# Arduino1.net
KiCad netlist of a schematic drawn in EAGLE
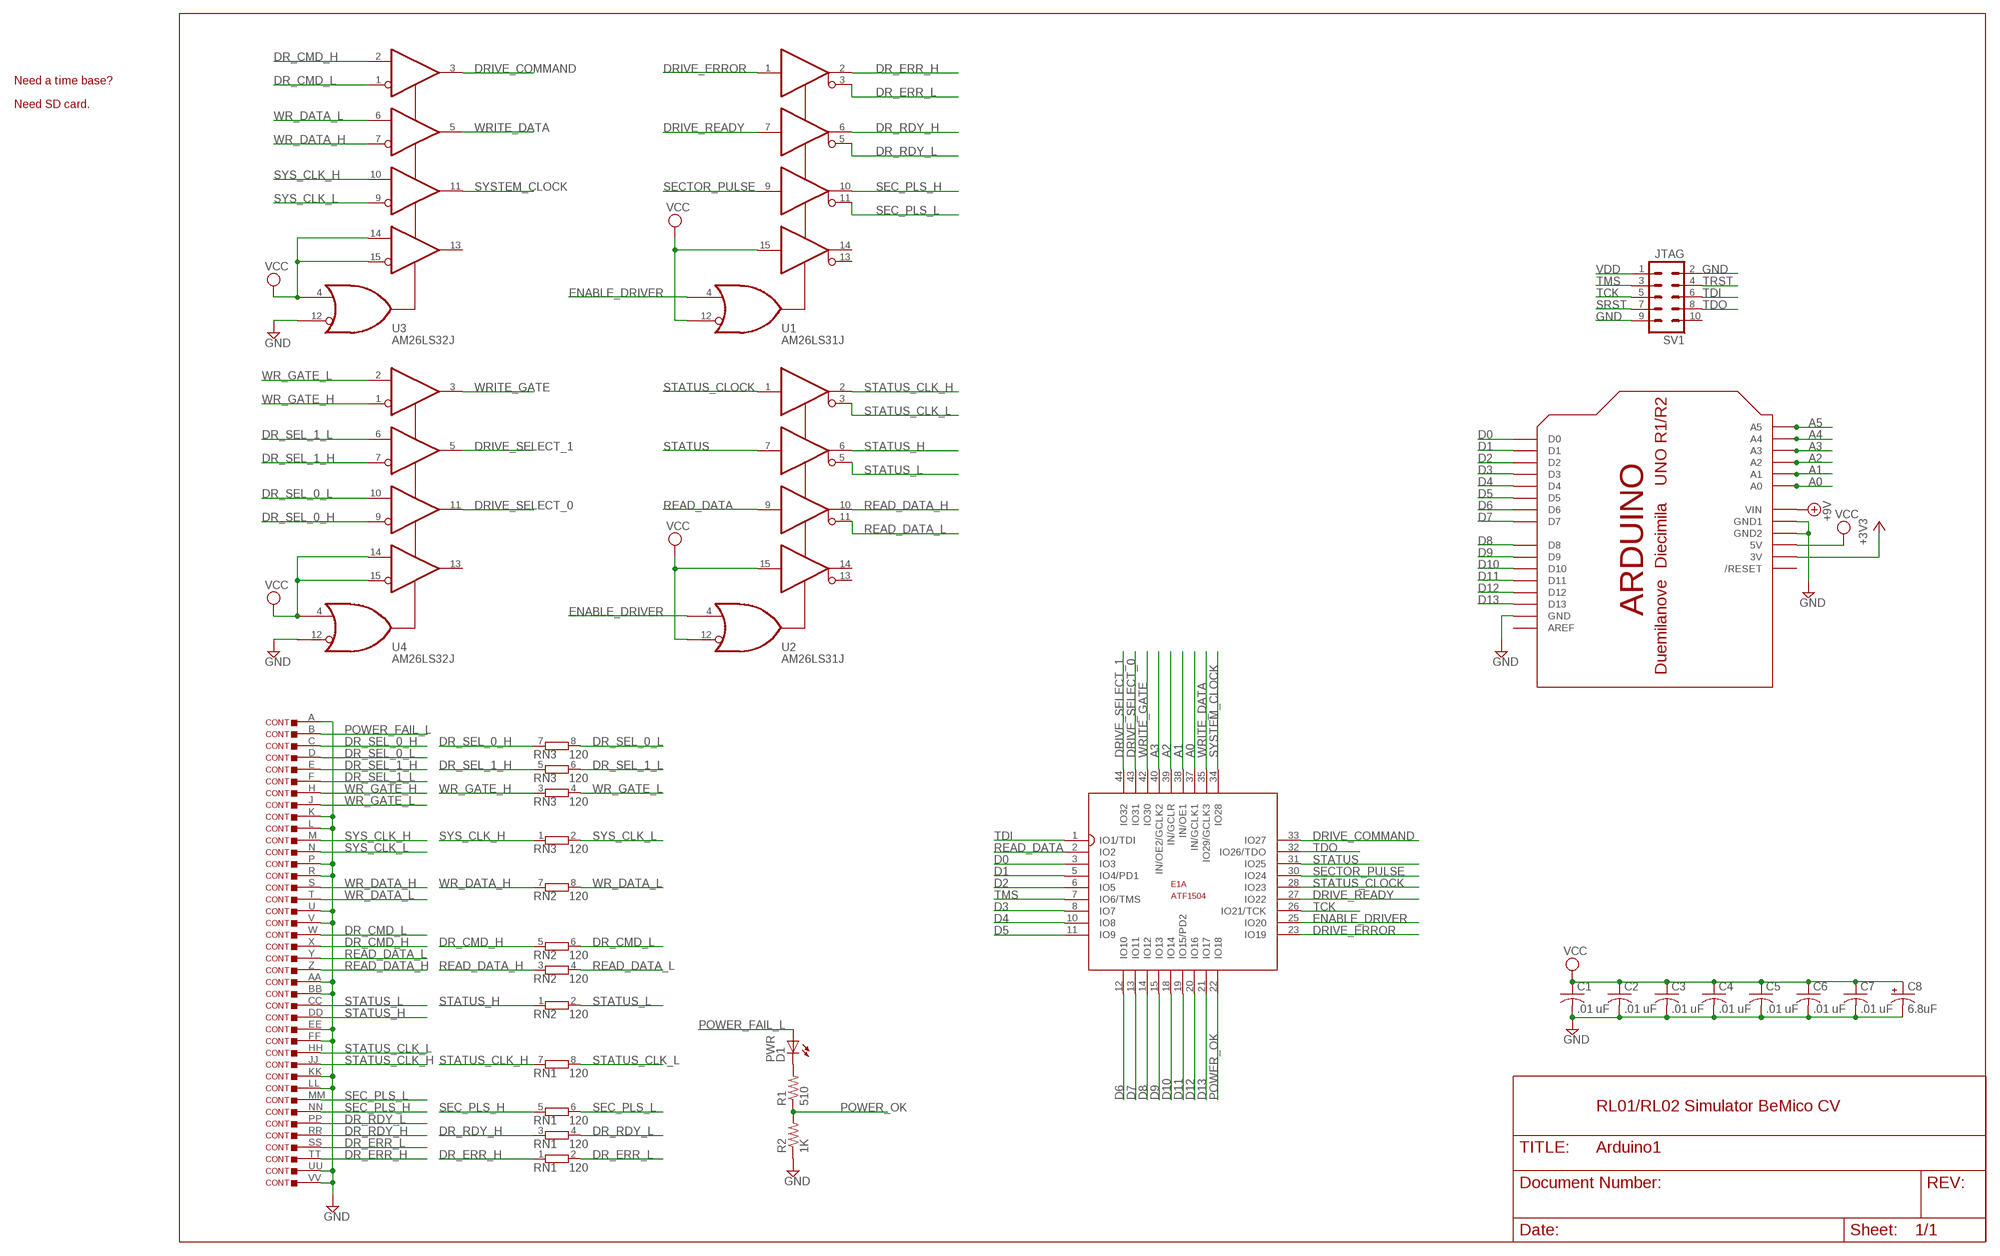
[diagram p0: schematic, sheet 1]

(export (version "E")
  (design (tool "Eeschema 10.0.6"))
  (components
    (comp (ref "C1")
      (value ".01 uF")
      (footprint "eagle-import:C050-025X075")
      (libsource (lib "eagle-import") (part "C-US050-025X075"))
    )
    (comp (ref "C2")
      (value ".01 uF")
      (footprint "eagle-import:C050-025X075")
      (libsource (lib "eagle-import") (part "C-US050-025X075"))
    )
    (comp (ref "C3")
      (value ".01 uF")
      (footprint "eagle-import:C050-025X075")
      (libsource (lib "eagle-import") (part "C-US050-025X075"))
    )
    (comp (ref "C4")
      (value ".01 uF")
      (footprint "eagle-import:C050-025X075")
      (libsource (lib "eagle-import") (part "C-US050-025X075"))
    )
    (comp (ref "C5")
      (value ".01 uF")
      (footprint "eagle-import:C050-025X075")
      (libsource (lib "eagle-import") (part "C-US050-025X075"))
    )
    (comp (ref "C6")
      (value ".01 uF")
      (footprint "eagle-import:C050-025X075")
      (libsource (lib "eagle-import") (part "C-US050-025X075"))
    )
    (comp (ref "C7")
      (value ".01 uF")
      (footprint "eagle-import:C050-025X075")
      (libsource (lib "eagle-import") (part "C-US050-025X075"))
    )
    (comp (ref "C8")
      (value "6.8uF")
      (footprint "eagle-import:E5-5")
      (libsource (lib "eagle-import") (part "CPOL-USE5-5"))
    )
    (comp (ref "CONT")
      (value "DEC40PINSV")
      (footprint "eagle-import:DEC40PINV")
      (libsource (lib "eagle-import") (part "DEC40PINSV"))
    )
    (comp (ref "D1")
      (value "PWR")
      (footprint "eagle-import:LED5MM")
      (libsource (lib "eagle-import") (part "LED5MM"))
    )
    (comp (ref "E1")
      (value "ATF1504")
      (footprint "eagle-import:TQFP44")
      (libsource (lib "eagle-import") (part "ATF150X44TQFP"))
    )
    (comp (ref "R1")
      (value "510")
      (footprint "eagle-import:0207_10")
      (libsource (lib "eagle-import") (part "R-US_0207/10"))
    )
    (comp (ref "R2")
      (value "1K")
      (footprint "eagle-import:0207_10")
      (libsource (lib "eagle-import") (part "R-US_0207/10"))
    )
    (comp (ref "RN1")
      (value "120")
      (footprint "eagle-import:SIL8")
      (libsource (lib "eagle-import") (part "E4RP"))
    )
    (comp (ref "RN2")
      (value "120")
      (footprint "eagle-import:SIL8")
      (libsource (lib "eagle-import") (part "E4RP"))
    )
    (comp (ref "RN3")
      (value "120")
      (footprint "eagle-import:SIL8")
      (libsource (lib "eagle-import") (part "E4RP"))
    )
    (comp (ref "SV1")
      (value "JTAG")
      (footprint "eagle-import:ML10")
      (libsource (lib "eagle-import") (part "ML10"))
    )
    (comp (ref "U$3")
      (value "ARDUINOUNO")
      (footprint "eagle-import:ARDUINO")
      (libsource (lib "eagle-import") (part "ARDUINOUNO"))
    )
    (comp (ref "U1")
      (value "AM26LS31J")
      (footprint "eagle-import:SO16")
      (libsource (lib "eagle-import") (part "AM26LS31J"))
    )
    (comp (ref "U2")
      (value "AM26LS31J")
      (footprint "eagle-import:SO16")
      (libsource (lib "eagle-import") (part "AM26LS31J"))
    )
    (comp (ref "U3")
      (value "AM26LS32J")
      (footprint "eagle-import:SO16")
      (libsource (lib "eagle-import") (part "AM26LS32J"))
    )
    (comp (ref "U4")
      (value "AM26LS32J")
      (footprint "eagle-import:SO16")
      (libsource (lib "eagle-import") (part "AM26LS32J"))
    )
  )
  (nets
    (net (code "1") (name "+3V3") (class "Default")
      (node (ref "U$3") (pin "3V") (pinfunction "3V_3V") (pintype "power_in"))
    )
    (net (code "2") (name "+9V") (class "Default")
      (node (ref "U$3") (pin "VIN") (pinfunction "VIN_VIN") (pintype "power_in"))
    )
    (net (code "3") (name "/A0") (class "Default")
      (node (ref "E1") (pin "37") (pinfunction "IN/GCLK1_37") (pintype "input"))
      (node (ref "U$3") (pin "A0") (pinfunction "A0_A0") (pintype "bidirectional"))
    )
    (net (code "4") (name "/A1") (class "Default")
      (node (ref "E1") (pin "38") (pinfunction "IN/OE1_38") (pintype "input"))
      (node (ref "U$3") (pin "A1") (pinfunction "A1_A1") (pintype "bidirectional"))
    )
    (net (code "5") (name "/A2") (class "Default")
      (node (ref "E1") (pin "39") (pinfunction "IN/GCLR_39") (pintype "input"))
      (node (ref "U$3") (pin "A2") (pinfunction "A2_A2") (pintype "bidirectional"))
    )
    (net (code "6") (name "/A3") (class "Default")
      (node (ref "E1") (pin "40") (pinfunction "IN/OE2/GCLK2_40") (pintype "input"))
      (node (ref "U$3") (pin "A3") (pinfunction "A3_A3") (pintype "bidirectional"))
    )
    (net (code "7") (name "/A4") (class "Default")
      (node (ref "U$3") (pin "A4") (pinfunction "A4_A4") (pintype "bidirectional"))
    )
    (net (code "8") (name "/A5") (class "Default")
      (node (ref "U$3") (pin "A5") (pinfunction "A5_A5") (pintype "bidirectional"))
    )
    (net (code "9") (name "/D0") (class "Default")
      (node (ref "E1") (pin "3") (pinfunction "IO3_3") (pintype "bidirectional"))
      (node (ref "U$3") (pin "D0") (pinfunction "D0_D0") (pintype "bidirectional"))
    )
    (net (code "10") (name "/D1") (class "Default")
      (node (ref "E1") (pin "5") (pinfunction "IO4/PD1_5") (pintype "bidirectional"))
      (node (ref "U$3") (pin "D1") (pinfunction "D1_D1") (pintype "bidirectional"))
    )
    (net (code "11") (name "/D2") (class "Default")
      (node (ref "E1") (pin "6") (pinfunction "IO5_6") (pintype "bidirectional"))
      (node (ref "U$3") (pin "D2") (pinfunction "D2_D2") (pintype "bidirectional"))
    )
    (net (code "12") (name "/D3") (class "Default")
      (node (ref "E1") (pin "8") (pinfunction "IO7_8") (pintype "bidirectional"))
      (node (ref "U$3") (pin "D3") (pinfunction "D3_D3") (pintype "bidirectional"))
    )
    (net (code "13") (name "/D4") (class "Default")
      (node (ref "E1") (pin "10") (pinfunction "IO8_10") (pintype "bidirectional"))
      (node (ref "U$3") (pin "D4") (pinfunction "D4_D4") (pintype "bidirectional"))
    )
    (net (code "14") (name "/D5") (class "Default")
      (node (ref "E1") (pin "11") (pinfunction "IO9_11") (pintype "bidirectional"))
      (node (ref "U$3") (pin "D5") (pinfunction "D5_D5") (pintype "bidirectional"))
    )
    (net (code "15") (name "/D6") (class "Default")
      (node (ref "E1") (pin "12") (pinfunction "IO10_12") (pintype "bidirectional"))
      (node (ref "U$3") (pin "D6") (pinfunction "D6_D6") (pintype "bidirectional"))
    )
    (net (code "16") (name "/D7") (class "Default")
      (node (ref "E1") (pin "13") (pinfunction "IO11_13") (pintype "bidirectional"))
      (node (ref "U$3") (pin "D7") (pinfunction "D7_D7") (pintype "bidirectional"))
    )
    (net (code "17") (name "/D8") (class "Default")
      (node (ref "E1") (pin "14") (pinfunction "IO12_14") (pintype "bidirectional"))
      (node (ref "U$3") (pin "D8") (pinfunction "D8_D8") (pintype "bidirectional"))
    )
    (net (code "18") (name "/D9") (class "Default")
      (node (ref "E1") (pin "15") (pinfunction "IO13_15") (pintype "bidirectional"))
      (node (ref "U$3") (pin "D9") (pinfunction "D9_D9") (pintype "bidirectional"))
    )
    (net (code "19") (name "/D10") (class "Default")
      (node (ref "E1") (pin "18") (pinfunction "IO14_18") (pintype "bidirectional"))
      (node (ref "U$3") (pin "D10") (pinfunction "D10_D10") (pintype "bidirectional"))
    )
    (net (code "20") (name "/D11") (class "Default")
      (node (ref "E1") (pin "19") (pinfunction "IO15/PD2_19") (pintype "bidirectional"))
      (node (ref "U$3") (pin "D11") (pinfunction "D11_D11") (pintype "bidirectional"))
    )
    (net (code "21") (name "/D12") (class "Default")
      (node (ref "E1") (pin "20") (pinfunction "IO16_20") (pintype "bidirectional"))
      (node (ref "U$3") (pin "D12") (pinfunction "D12_D12") (pintype "bidirectional"))
    )
    (net (code "22") (name "/D13") (class "Default")
      (node (ref "E1") (pin "21") (pinfunction "IO17_21") (pintype "bidirectional"))
      (node (ref "U$3") (pin "D13") (pinfunction "D13_D13") (pintype "bidirectional"))
    )
    (net (code "23") (name "/DRIVE_COMMAND") (class "Default")
      (node (ref "E1") (pin "33") (pinfunction "IO27_33") (pintype "bidirectional"))
      (node (ref "U3") (pin "3") (pinfunction "Y1_3") (pintype "output"))
    )
    (net (code "24") (name "/DRIVE_ERROR") (class "Default")
      (node (ref "E1") (pin "23") (pinfunction "IO19_23") (pintype "bidirectional"))
      (node (ref "U1") (pin "1") (pinfunction "A1_1") (pintype "input"))
    )
    (net (code "25") (name "/DRIVE_READY") (class "Default")
      (node (ref "E1") (pin "27") (pinfunction "IO22_27") (pintype "bidirectional"))
      (node (ref "U1") (pin "7") (pinfunction "A2_7") (pintype "input"))
    )
    (net (code "26") (name "/DRIVE_SELECT_0") (class "Default")
      (node (ref "E1") (pin "43") (pinfunction "IO31_43") (pintype "bidirectional"))
      (node (ref "U4") (pin "11") (pinfunction "Y3_11") (pintype "output"))
    )
    (net (code "27") (name "/DRIVE_SELECT_1") (class "Default")
      (node (ref "E1") (pin "44") (pinfunction "IO32_44") (pintype "bidirectional"))
      (node (ref "U4") (pin "5") (pinfunction "Y2_5") (pintype "output"))
    )
    (net (code "28") (name "/DR_CMD_H") (class "Default")
      (node (ref "CONT") (pin "X") (pinfunction "P$2_X") (pintype "passive"))
      (node (ref "RN2") (pin "5") (pinfunction "1_5") (pintype "passive"))
      (node (ref "U3") (pin "2") (pinfunction "P1_2") (pintype "input"))
    )
    (net (code "29") (name "/DR_CMD_L") (class "Default")
      (node (ref "CONT") (pin "W") (pinfunction "P$2_W") (pintype "passive"))
      (node (ref "RN2") (pin "6") (pinfunction "2_6") (pintype "passive"))
      (node (ref "U3") (pin "1") (pinfunction "N1_1") (pintype "input"))
    )
    (net (code "30") (name "/DR_ERR_H") (class "Default")
      (node (ref "CONT") (pin "TT") (pinfunction "P$2_TT") (pintype "passive"))
      (node (ref "RN1") (pin "1") (pinfunction "1_1") (pintype "passive"))
      (node (ref "U1") (pin "2") (pinfunction "Y1_2") (pintype "output"))
    )
    (net (code "31") (name "/DR_ERR_L") (class "Default")
      (node (ref "CONT") (pin "SS") (pinfunction "P$2_SS") (pintype "passive"))
      (node (ref "RN1") (pin "2") (pinfunction "2_2") (pintype "passive"))
      (node (ref "U1") (pin "3") (pinfunction "Z1_3") (pintype "output"))
    )
    (net (code "32") (name "/DR_RDY_H") (class "Default")
      (node (ref "CONT") (pin "RR") (pinfunction "P$2_RR") (pintype "passive"))
      (node (ref "RN1") (pin "3") (pinfunction "1_3") (pintype "passive"))
      (node (ref "U1") (pin "6") (pinfunction "Y2_6") (pintype "output"))
    )
    (net (code "33") (name "/DR_RDY_L") (class "Default")
      (node (ref "CONT") (pin "PP") (pinfunction "P$2_PP") (pintype "passive"))
      (node (ref "RN1") (pin "4") (pinfunction "2_4") (pintype "passive"))
      (node (ref "U1") (pin "5") (pinfunction "Z2_5") (pintype "output"))
    )
    (net (code "34") (name "/DR_SEL_0_H") (class "Default")
      (node (ref "CONT") (pin "C") (pinfunction "P$2_C") (pintype "passive"))
      (node (ref "RN3") (pin "7") (pinfunction "1_7") (pintype "passive"))
      (node (ref "U4") (pin "9") (pinfunction "N3_9") (pintype "input"))
    )
    (net (code "35") (name "/DR_SEL_0_L") (class "Default")
      (node (ref "CONT") (pin "D") (pinfunction "P$2_D") (pintype "passive"))
      (node (ref "RN3") (pin "8") (pinfunction "2_8") (pintype "passive"))
      (node (ref "U4") (pin "10") (pinfunction "P3_10") (pintype "input"))
    )
    (net (code "36") (name "/DR_SEL_1_H") (class "Default")
      (node (ref "CONT") (pin "E") (pinfunction "P$2_E") (pintype "passive"))
      (node (ref "RN3") (pin "5") (pinfunction "1_5") (pintype "passive"))
      (node (ref "U4") (pin "7") (pinfunction "N2_7") (pintype "input"))
    )
    (net (code "37") (name "/DR_SEL_1_L") (class "Default")
      (node (ref "CONT") (pin "F") (pinfunction "P$2_F") (pintype "passive"))
      (node (ref "RN3") (pin "6") (pinfunction "2_6") (pintype "passive"))
      (node (ref "U4") (pin "6") (pinfunction "P2_6") (pintype "input"))
    )
    (net (code "38") (name "/ENABLE_DRIVER") (class "Default")
      (node (ref "E1") (pin "25") (pinfunction "IO20_25") (pintype "bidirectional"))
      (node (ref "U1") (pin "4") (pinfunction "G_4") (pintype "input"))
      (node (ref "U2") (pin "4") (pinfunction "G_4") (pintype "input"))
    )
    (net (code "39") (name "/POWER_FAIL_L") (class "Default")
      (node (ref "CONT") (pin "B") (pinfunction "P$2_B") (pintype "passive"))
      (node (ref "D1") (pin "A") (pinfunction "A_A") (pintype "passive"))
    )
    (net (code "40") (name "/POWER_OK") (class "Default")
      (node (ref "E1") (pin "22") (pinfunction "IO18_22") (pintype "bidirectional"))
      (node (ref "R1") (pin "1") (pinfunction "1_1") (pintype "passive"))
      (node (ref "R2") (pin "2") (pinfunction "2_2") (pintype "passive"))
    )
    (net (code "41") (name "/READ_DATA") (class "Default")
      (node (ref "E1") (pin "2") (pinfunction "IO2_2") (pintype "bidirectional"))
      (node (ref "U2") (pin "9") (pinfunction "A3_9") (pintype "input"))
    )
    (net (code "42") (name "/READ_DATA_H") (class "Default")
      (node (ref "CONT") (pin "Z") (pinfunction "P$2_Z") (pintype "passive"))
      (node (ref "RN2") (pin "3") (pinfunction "1_3") (pintype "passive"))
      (node (ref "U2") (pin "10") (pinfunction "Y3_10") (pintype "output"))
    )
    (net (code "43") (name "/READ_DATA_L") (class "Default")
      (node (ref "CONT") (pin "Y") (pinfunction "P$2_Y") (pintype "passive"))
      (node (ref "RN2") (pin "4") (pinfunction "2_4") (pintype "passive"))
      (node (ref "U2") (pin "11") (pinfunction "Z3_11") (pintype "output"))
    )
    (net (code "44") (name "/SECTOR_PULSE") (class "Default")
      (node (ref "E1") (pin "30") (pinfunction "IO24_30") (pintype "bidirectional"))
      (node (ref "U1") (pin "9") (pinfunction "A3_9") (pintype "input"))
    )
    (net (code "45") (name "/SEC_PLS_H") (class "Default")
      (node (ref "CONT") (pin "NN") (pinfunction "P$2_NN") (pintype "passive"))
      (node (ref "RN1") (pin "5") (pinfunction "1_5") (pintype "passive"))
      (node (ref "U1") (pin "10") (pinfunction "Y3_10") (pintype "output"))
    )
    (net (code "46") (name "/SEC_PLS_L") (class "Default")
      (node (ref "CONT") (pin "MM") (pinfunction "P$2_MM") (pintype "passive"))
      (node (ref "RN1") (pin "6") (pinfunction "2_6") (pintype "passive"))
      (node (ref "U1") (pin "11") (pinfunction "Z3_11") (pintype "output"))
    )
    (net (code "47") (name "/SRST") (class "Default")
      (node (ref "SV1") (pin "7") (pinfunction "7_7") (pintype "passive"))
    )
    (net (code "48") (name "/STATUS") (class "Default")
      (node (ref "E1") (pin "31") (pinfunction "IO25_31") (pintype "bidirectional"))
      (node (ref "U2") (pin "7") (pinfunction "A2_7") (pintype "input"))
    )
    (net (code "49") (name "/STATUS_CLK_H") (class "Default")
      (node (ref "CONT") (pin "JJ") (pinfunction "P$2_JJ") (pintype "passive"))
      (node (ref "RN1") (pin "7") (pinfunction "1_7") (pintype "passive"))
      (node (ref "U2") (pin "2") (pinfunction "Y1_2") (pintype "output"))
    )
    (net (code "50") (name "/STATUS_CLK_L") (class "Default")
      (node (ref "CONT") (pin "HH") (pinfunction "P$2_HH") (pintype "passive"))
      (node (ref "RN1") (pin "8") (pinfunction "2_8") (pintype "passive"))
      (node (ref "U2") (pin "3") (pinfunction "Z1_3") (pintype "output"))
    )
    (net (code "51") (name "/STATUS_CLOCK") (class "Default")
      (node (ref "E1") (pin "28") (pinfunction "IO23_28") (pintype "bidirectional"))
      (node (ref "U2") (pin "1") (pinfunction "A1_1") (pintype "input"))
    )
    (net (code "52") (name "/STATUS_H") (class "Default")
      (node (ref "CONT") (pin "DD") (pinfunction "P$2_DD") (pintype "passive"))
      (node (ref "RN2") (pin "1") (pinfunction "1_1") (pintype "passive"))
      (node (ref "U2") (pin "6") (pinfunction "Y2_6") (pintype "output"))
    )
    (net (code "53") (name "/STATUS_L") (class "Default")
      (node (ref "CONT") (pin "CC") (pinfunction "P$2_CC") (pintype "passive"))
      (node (ref "RN2") (pin "2") (pinfunction "2_2") (pintype "passive"))
      (node (ref "U2") (pin "5") (pinfunction "Z2_5") (pintype "output"))
    )
    (net (code "54") (name "/SYSTEM_CLOCK") (class "Default")
      (node (ref "E1") (pin "34") (pinfunction "IO28_34") (pintype "bidirectional"))
      (node (ref "U3") (pin "11") (pinfunction "Y3_11") (pintype "output"))
    )
    (net (code "55") (name "/SYS_CLK_H") (class "Default")
      (node (ref "CONT") (pin "M") (pinfunction "P$2_M") (pintype "passive"))
      (node (ref "RN3") (pin "1") (pinfunction "1_1") (pintype "passive"))
      (node (ref "U3") (pin "10") (pinfunction "P3_10") (pintype "input"))
    )
    (net (code "56") (name "/SYS_CLK_L") (class "Default")
      (node (ref "CONT") (pin "N") (pinfunction "P$2_N") (pintype "passive"))
      (node (ref "RN3") (pin "2") (pinfunction "2_2") (pintype "passive"))
      (node (ref "U3") (pin "9") (pinfunction "N3_9") (pintype "input"))
    )
    (net (code "57") (name "/TCK") (class "Default")
      (node (ref "E1") (pin "26") (pinfunction "IO21/TCK_26") (pintype "bidirectional"))
      (node (ref "SV1") (pin "5") (pinfunction "5_5") (pintype "passive"))
    )
    (net (code "58") (name "/TDI") (class "Default")
      (node (ref "E1") (pin "1") (pinfunction "IO1/TDI_1") (pintype "bidirectional"))
      (node (ref "SV1") (pin "6") (pinfunction "6_6") (pintype "passive"))
    )
    (net (code "59") (name "/TDO") (class "Default")
      (node (ref "E1") (pin "32") (pinfunction "IO26/TDO_32") (pintype "bidirectional"))
      (node (ref "SV1") (pin "8") (pinfunction "8_8") (pintype "passive"))
    )
    (net (code "60") (name "/TMS") (class "Default")
      (node (ref "E1") (pin "7") (pinfunction "IO6/TMS_7") (pintype "bidirectional"))
      (node (ref "SV1") (pin "3") (pinfunction "3_3") (pintype "passive"))
    )
    (net (code "61") (name "/TRST") (class "Default")
      (node (ref "SV1") (pin "4") (pinfunction "4_4") (pintype "passive"))
    )
    (net (code "62") (name "/VDD") (class "Default")
      (node (ref "SV1") (pin "1") (pinfunction "1_1") (pintype "passive"))
    )
    (net (code "63") (name "/WRITE_DATA") (class "Default")
      (node (ref "E1") (pin "35") (pinfunction "IO29/GCLK3_35") (pintype "bidirectional"))
      (node (ref "U3") (pin "5") (pinfunction "Y2_5") (pintype "output"))
    )
    (net (code "64") (name "/WRITE_GATE") (class "Default")
      (node (ref "E1") (pin "42") (pinfunction "IO30_42") (pintype "bidirectional"))
      (node (ref "U4") (pin "3") (pinfunction "Y1_3") (pintype "output"))
    )
    (net (code "65") (name "/WR_DATA_H") (class "Default")
      (node (ref "CONT") (pin "S") (pinfunction "P$2_S") (pintype "passive"))
      (node (ref "RN2") (pin "7") (pinfunction "1_7") (pintype "passive"))
      (node (ref "U3") (pin "7") (pinfunction "N2_7") (pintype "input"))
    )
    (net (code "66") (name "/WR_DATA_L") (class "Default")
      (node (ref "CONT") (pin "T") (pinfunction "P$2_T") (pintype "passive"))
      (node (ref "RN2") (pin "8") (pinfunction "2_8") (pintype "passive"))
      (node (ref "U3") (pin "6") (pinfunction "P2_6") (pintype "input"))
    )
    (net (code "67") (name "/WR_GATE_H") (class "Default")
      (node (ref "CONT") (pin "H") (pinfunction "P$2_H") (pintype "passive"))
      (node (ref "RN3") (pin "3") (pinfunction "1_3") (pintype "passive"))
      (node (ref "U4") (pin "1") (pinfunction "N1_1") (pintype "input"))
    )
    (net (code "68") (name "/WR_GATE_L") (class "Default")
      (node (ref "CONT") (pin "J") (pinfunction "P$2_J") (pintype "passive"))
      (node (ref "RN3") (pin "4") (pinfunction "2_4") (pintype "passive"))
      (node (ref "U4") (pin "2") (pinfunction "P1_2") (pintype "input"))
    )
    (net (code "69") (name "GND") (class "Default")
      (node (ref "C1") (pin "2") (pinfunction "2_2") (pintype "passive"))
      (node (ref "C2") (pin "2") (pinfunction "2_2") (pintype "passive"))
      (node (ref "C3") (pin "2") (pinfunction "2_2") (pintype "passive"))
      (node (ref "C4") (pin "2") (pinfunction "2_2") (pintype "passive"))
      (node (ref "C5") (pin "2") (pinfunction "2_2") (pintype "passive"))
      (node (ref "C6") (pin "2") (pinfunction "2_2") (pintype "passive"))
      (node (ref "C7") (pin "2") (pinfunction "2_2") (pintype "passive"))
      (node (ref "C8") (pin "-") (pinfunction "-_-") (pintype "passive"))
      (node (ref "CONT") (pin "A") (pinfunction "P$2_A") (pintype "passive"))
      (node (ref "CONT") (pin "AA") (pinfunction "P$2_AA") (pintype "passive"))
      (node (ref "CONT") (pin "BB") (pinfunction "P$2_BB") (pintype "passive"))
      (node (ref "CONT") (pin "EE") (pinfunction "P$2_EE") (pintype "passive"))
      (node (ref "CONT") (pin "FF") (pinfunction "P$2_FF") (pintype "passive"))
      (node (ref "CONT") (pin "K") (pinfunction "P$2_K") (pintype "passive"))
      (node (ref "CONT") (pin "KK") (pinfunction "P$2_KK") (pintype "passive"))
      (node (ref "CONT") (pin "L") (pinfunction "P$2_L") (pintype "passive"))
      (node (ref "CONT") (pin "LL") (pinfunction "P$2_LL") (pintype "passive"))
      (node (ref "CONT") (pin "P") (pinfunction "P$2_P") (pintype "passive"))
      (node (ref "CONT") (pin "R") (pinfunction "P$2_R") (pintype "passive"))
      (node (ref "CONT") (pin "U") (pinfunction "P$2_U") (pintype "passive"))
      (node (ref "CONT") (pin "UU") (pinfunction "P$2_UU") (pintype "passive"))
      (node (ref "CONT") (pin "V") (pinfunction "P$2_V") (pintype "passive"))
      (node (ref "CONT") (pin "VV") (pinfunction "P$2_VV") (pintype "passive"))
      (node (ref "R2") (pin "1") (pinfunction "1_1") (pintype "passive"))
      (node (ref "SV1") (pin "2") (pinfunction "2_2") (pintype "passive"))
      (node (ref "SV1") (pin "9") (pinfunction "9_9") (pintype "passive"))
      (node (ref "U$3") (pin "GND") (pinfunction "GND_GND") (pintype "power_in"))
      (node (ref "U$3") (pin "GND1") (pinfunction "GND1_GND1") (pintype "power_in"))
      (node (ref "U$3") (pin "GND2") (pinfunction "GND2_GND2") (pintype "power_in"))
      (node (ref "U3") (pin "12") (pinfunction "~{G}_12") (pintype "input"))
      (node (ref "U4") (pin "12") (pinfunction "~{G}_12") (pintype "input"))
    )
    (net (code "70") (name "Net-(D1-C)") (class "Default")
      (node (ref "D1") (pin "K") (pinfunction "C_K") (pintype "passive"))
      (node (ref "R1") (pin "2") (pinfunction "2_2") (pintype "passive"))
    )
    (net (code "71") (name "VCC") (class "Default")
      (node (ref "C1") (pin "1") (pinfunction "1_1") (pintype "passive"))
      (node (ref "C2") (pin "1") (pinfunction "1_1") (pintype "passive"))
      (node (ref "C3") (pin "1") (pinfunction "1_1") (pintype "passive"))
      (node (ref "C4") (pin "1") (pinfunction "1_1") (pintype "passive"))
      (node (ref "C5") (pin "1") (pinfunction "1_1") (pintype "passive"))
      (node (ref "C6") (pin "1") (pinfunction "1_1") (pintype "passive"))
      (node (ref "C7") (pin "1") (pinfunction "1_1") (pintype "passive"))
      (node (ref "C8") (pin "+") (pinfunction "+_+") (pintype "passive"))
      (node (ref "U$3") (pin "5V") (pinfunction "5V_5V") (pintype "power_in"))
      (node (ref "U1") (pin "12") (pinfunction "~{G}_12") (pintype "input"))
      (node (ref "U1") (pin "15") (pinfunction "A4_15") (pintype "input"))
      (node (ref "U2") (pin "12") (pinfunction "~{G}_12") (pintype "input"))
      (node (ref "U2") (pin "15") (pinfunction "A4_15") (pintype "input"))
      (node (ref "U3") (pin "14") (pinfunction "P4_14") (pintype "input"))
      (node (ref "U3") (pin "15") (pinfunction "N4_15") (pintype "input"))
      (node (ref "U3") (pin "4") (pinfunction "G_4") (pintype "input"))
      (node (ref "U4") (pin "14") (pinfunction "P4_14") (pintype "input"))
      (node (ref "U4") (pin "15") (pinfunction "N4_15") (pintype "input"))
      (node (ref "U4") (pin "4") (pinfunction "G_4") (pintype "input"))
    )
    (net (code "72") (name "unconnected-(SV1-Pad10)") (class "Default")
      (node (ref "SV1") (pin "10") (pinfunction "10_10") (pintype "passive"))
    )
    (net (code "73") (name "unconnected-(U$3-PadAREF)") (class "Default")
      (node (ref "U$3") (pin "AREF") (pinfunction "AREF_AREF") (pintype "bidirectional"))
    )
    (net (code "74") (name "unconnected-(U$3-{slash}RESET-PadRESET)") (class "Default")
      (node (ref "U$3") (pin "RESET") (pinfunction "/RESET_RESET") (pintype "bidirectional"))
    )
    (net (code "75") (name "unconnected-(U1A-Y4-Pad14)") (class "Default")
      (node (ref "U1") (pin "14") (pinfunction "Y4_14") (pintype "output"))
    )
    (net (code "76") (name "unconnected-(U1A-Z4-Pad13)") (class "Default")
      (node (ref "U1") (pin "13") (pinfunction "Z4_13") (pintype "output"))
    )
    (net (code "77") (name "unconnected-(U2A-Y4-Pad14)") (class "Default")
      (node (ref "U2") (pin "14") (pinfunction "Y4_14") (pintype "output"))
    )
    (net (code "78") (name "unconnected-(U2A-Z4-Pad13)") (class "Default")
      (node (ref "U2") (pin "13") (pinfunction "Z4_13") (pintype "output"))
    )
    (net (code "79") (name "unconnected-(U3A-Y4-Pad13)") (class "Default")
      (node (ref "U3") (pin "13") (pinfunction "Y4_13") (pintype "output"))
    )
    (net (code "80") (name "unconnected-(U4A-Y4-Pad13)") (class "Default")
      (node (ref "U4") (pin "13") (pinfunction "Y4_13") (pintype "output"))
    )
  )
)
